# CC-S10-V00-PSU-5V.net
KiCad netlist of a schematic drawn in Altium Designer
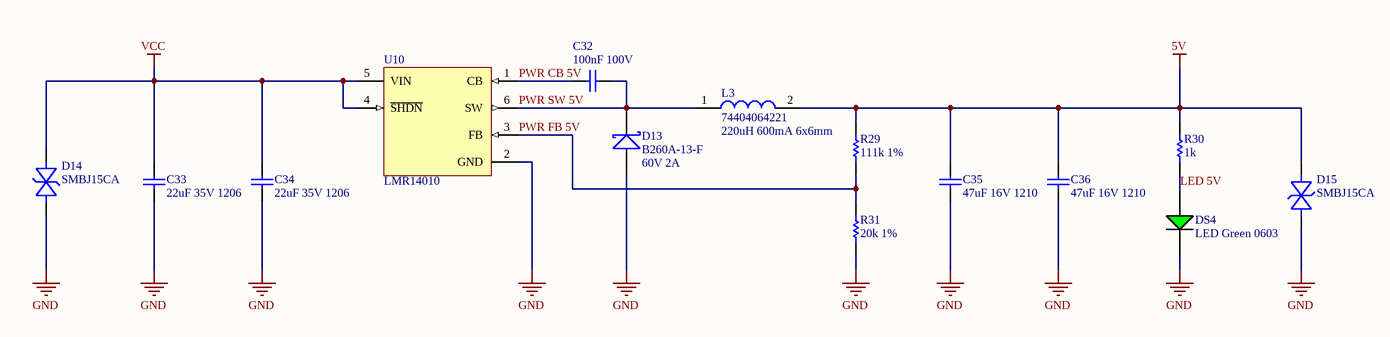
[diagram p0: CC-S10-V00-PSU-5V.SchDoc]

(export (version "E")
  (design (tool "Eeschema 10.0.6"))
  (components
    (comp (ref "C32")
      (value "100nF 100V")
      (footprint "Cap_Ceramic_0603")
      (description "Capacitor, Ceramic, SMD, 100nF, 100V, 5%, X7R, 0603")
      (libsource (lib "StandardCapacitors") (part "100nF 100V 5% X7R 0603"))
    )
    (comp (ref "C33")
      (value "22uF 35V 1206")
      (footprint "Cap_Ceramic_1206")
      (description "Capacitor, Ceramic, SMD, 22uF, 35V, 10%, X7R, 1206")
      (libsource (lib "StandardCapacitors") (part "22uF 35V 10% X7R 1206"))
    )
    (comp (ref "C34")
      (value "22uF 35V 1206")
      (footprint "Cap_Ceramic_1206")
      (description "Capacitor, Ceramic, SMD, 22uF, 35V, 10%, X7R, 1206")
      (libsource (lib "StandardCapacitors") (part "22uF 35V 10% X7R 1206"))
    )
    (comp (ref "C35")
      (value "47uF 16V 1210")
      (footprint "Cap_Ceramic_1210")
      (description "Capacitor, Ceramic, SMD, 47uF, 16V, 5%, X7R, 1210")
      (libsource (lib "StandardCapacitors") (part "47uF 16V 10% X7R 1210"))
    )
    (comp (ref "C36")
      (value "47uF 16V 1210")
      (footprint "Cap_Ceramic_1210")
      (description "Capacitor, Ceramic, SMD, 47uF, 16V, 5%, X7R, 1210")
      (libsource (lib "StandardCapacitors") (part "47uF 16V 10% X7R 1210"))
    )
    (comp (ref "D13")
      (value "B260A-13-F")
      (footprint "SMA")
      (description "Diode, Schottky Barrier Rectifier, 60 V, 2 A, B260A-13-F")
      (libsource (lib "QUTMS_DiodeLibrary") (part "B260A-13-F"))
    )
    (comp (ref "D14")
      (value "SMBJ15CA")
      (footprint "SMB")
      (description "Diode, SMD, TVS Diode, 15V 24.4V, DO214AA/SMB")
      (libsource (lib "QUTMS_DiodeLibrary") (part "SMBJ15CA"))
    )
    (comp (ref "D15")
      (value "SMBJ15CA")
      (footprint "SMB")
      (description "Diode, SMD, TVS Diode, 15V 24.4V, DO214AA/SMB")
      (libsource (lib "QUTMS_DiodeLibrary") (part "SMBJ15CA"))
    )
    (comp (ref "DS4")
      (value "LED Green 0603")
      (footprint "LED GREEN 0603")
      (libsource (lib "QUTMS_LEDLibrary") (part "LED Green 0603"))
    )
    (comp (ref "L3")
      (value "74404064221")
      (footprint "Inductor_6x6mm")
      (description "FIXED IND 220UH 660MA 850 MOHM")
      (libsource (lib "QUTMS_InductorLibrary") (part "74404064221"))
    )
    (comp (ref "R29")
      (value "111k 1%")
      (footprint "Res_ThinFilm_0603")
      (description "Resistor, SMD, 111k, 0.1W, 5%, 0603")
      (libsource (lib "StandardResistors") (part "111k 1% 0603"))
    )
    (comp (ref "R30")
      (value "1k")
      (footprint "Res_ThinFilm_0603")
      (description "Resistor, SMD, 1k, 0.1W, 5%, 0603")
      (libsource (lib "StandardResistors") (part "1k 5% 0603"))
    )
    (comp (ref "R31")
      (value "20k 1%")
      (footprint "Res_ThinFilm_0603")
      (description "Resistor, SMD, 20k, 0.1W, 1%, 0603")
      (libsource (lib "StandardResistors") (part "20k 1% 0603"))
    )
    (comp (ref "U10")
      (value "LMR14010")
      (footprint "LMR14010")
      (libsource (lib "QUTMS_PowerSupplyLibrary") (part "LMR14010"))
    )
  )
  (nets
    (net (code "1") (name "/LED 5V") (class "Default")
      (node (ref "DS4") (pin "1") (pinfunction "A_1") (pintype "passive"))
      (node (ref "R30") (pin "1") (pinfunction "1_1") (pintype "passive"))
    )
    (net (code "2") (name "/PWR CB 5V") (class "Default")
      (node (ref "C32") (pin "1") (pinfunction "1_1") (pintype "passive"))
      (node (ref "U10") (pin "1") (pinfunction "CB_1") (pintype "input"))
    )
    (net (code "3") (name "/PWR FB 5V") (class "Default")
      (node (ref "R29") (pin "1") (pinfunction "1_1") (pintype "passive"))
      (node (ref "R31") (pin "2") (pinfunction "2_2") (pintype "passive"))
      (node (ref "U10") (pin "3") (pinfunction "FB_3") (pintype "input"))
    )
    (net (code "4") (name "/PWR SW 5V") (class "Default")
      (node (ref "C32") (pin "2") (pinfunction "2_2") (pintype "passive"))
      (node (ref "D13") (pin "K") (pinfunction "K_K") (pintype "passive"))
      (node (ref "L3") (pin "1") (pinfunction "1_1") (pintype "passive"))
      (node (ref "U10") (pin "6") (pinfunction "SW_6") (pintype "output"))
    )
    (net (code "5") (name "5V") (class "Default")
      (node (ref "C35") (pin "2") (pinfunction "2_2") (pintype "passive"))
      (node (ref "C36") (pin "2") (pinfunction "2_2") (pintype "passive"))
      (node (ref "D15") (pin "K") (pinfunction "Cathode_K") (pintype "passive"))
      (node (ref "L3") (pin "2") (pinfunction "2_2") (pintype "passive"))
      (node (ref "R29") (pin "2") (pinfunction "2_2") (pintype "passive"))
      (node (ref "R30") (pin "2") (pinfunction "2_2") (pintype "passive"))
    )
    (net (code "6") (name "GND") (class "Default")
      (node (ref "C33") (pin "1") (pinfunction "1_1") (pintype "passive"))
      (node (ref "C34") (pin "1") (pinfunction "1_1") (pintype "passive"))
      (node (ref "C35") (pin "1") (pinfunction "1_1") (pintype "passive"))
      (node (ref "C36") (pin "1") (pinfunction "1_1") (pintype "passive"))
      (node (ref "D13") (pin "A") (pinfunction "A_A") (pintype "passive"))
      (node (ref "D14") (pin "A") (pinfunction "Anode_A") (pintype "passive"))
      (node (ref "D15") (pin "A") (pinfunction "Anode_A") (pintype "passive"))
      (node (ref "DS4") (pin "2") (pinfunction "C_2") (pintype "passive"))
      (node (ref "R31") (pin "1") (pinfunction "1_1") (pintype "passive"))
      (node (ref "U10") (pin "2") (pinfunction "GND_2") (pintype "power_in"))
    )
    (net (code "7") (name "VCC") (class "Default")
      (node (ref "C33") (pin "2") (pinfunction "2_2") (pintype "passive"))
      (node (ref "C34") (pin "2") (pinfunction "2_2") (pintype "passive"))
      (node (ref "D14") (pin "K") (pinfunction "Cathode_K") (pintype "passive"))
      (node (ref "U10") (pin "4") (pinfunction "~{SHDN}_4") (pintype "input"))
      (node (ref "U10") (pin "5") (pinfunction "VIN_5") (pintype "power_in"))
    )
  )
)
